# reg_lator_eagle.net
KiCad netlist of a schematic drawn in EAGLE
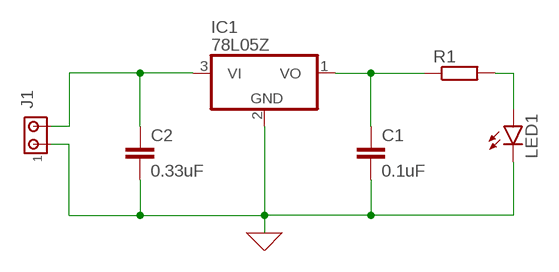
[diagram p0: schematic, sheet 1]

(export (version "E")
  (design (tool "Eeschema 10.0.6"))
  (components
    (comp (ref "C1")
      (value "0.1uF")
      (footprint "eagle-import:C2.5-3")
      (libsource (lib "eagle-import") (part "C2,5-3"))
    )
    (comp (ref "C2")
      (value "0.33uF")
      (footprint "eagle-import:C2.5-3")
      (libsource (lib "eagle-import") (part "C2,5-3"))
    )
    (comp (ref "IC1")
      (value "78L05Z")
      (footprint "eagle-import:TO92")
      (libsource (lib "eagle-import") (part "78ZL05"))
    )
    (comp (ref "J1")
      (value "MTA02-100")
      (footprint "eagle-import:10X02MTA")
      (libsource (lib "eagle-import") (part "MTA02-100"))
    )
    (comp (ref "LED1")
      (value "LED5MM")
      (footprint "eagle-import:LED5MM")
      (libsource (lib "eagle-import") (part "LED5MM"))
    )
    (comp (ref "R1")
      (value "R-EU_0207/10")
      (footprint "eagle-import:0207_10")
      (libsource (lib "eagle-import") (part "R-EU_0207/10"))
    )
  )
  (nets
    (net (code "1") (name "GND") (class "Default")
      (node (ref "C1") (pin "2") (pinfunction "2_2") (pintype "passive"))
      (node (ref "C2") (pin "2") (pinfunction "2_2") (pintype "passive"))
      (node (ref "IC1") (pin "2") (pinfunction "GND_2") (pintype "passive"))
      (node (ref "J1") (pin "1") (pinfunction "1_1") (pintype "passive"))
      (node (ref "LED1") (pin "K") (pinfunction "C_K") (pintype "passive"))
    )
    (net (code "2") (name "Net-(IC1-VI)") (class "Default")
      (node (ref "C2") (pin "1") (pinfunction "1_1") (pintype "passive"))
      (node (ref "IC1") (pin "3") (pinfunction "VI_3") (pintype "input"))
      (node (ref "J1") (pin "2") (pinfunction "2_2") (pintype "passive"))
    )
    (net (code "3") (name "Net-(IC1-VO)") (class "Default")
      (node (ref "C1") (pin "1") (pinfunction "1_1") (pintype "passive"))
      (node (ref "IC1") (pin "1") (pinfunction "VO_1") (pintype "passive"))
      (node (ref "R1") (pin "1") (pinfunction "1_1") (pintype "passive"))
    )
    (net (code "4") (name "Net-(LED1-PadA)") (class "Default")
      (node (ref "LED1") (pin "A") (pinfunction "A_A") (pintype "passive"))
      (node (ref "R1") (pin "2") (pinfunction "2_2") (pintype "passive"))
    )
  )
)
